# buisiness_card.net
KiCad netlist of a schematic drawn in EAGLE
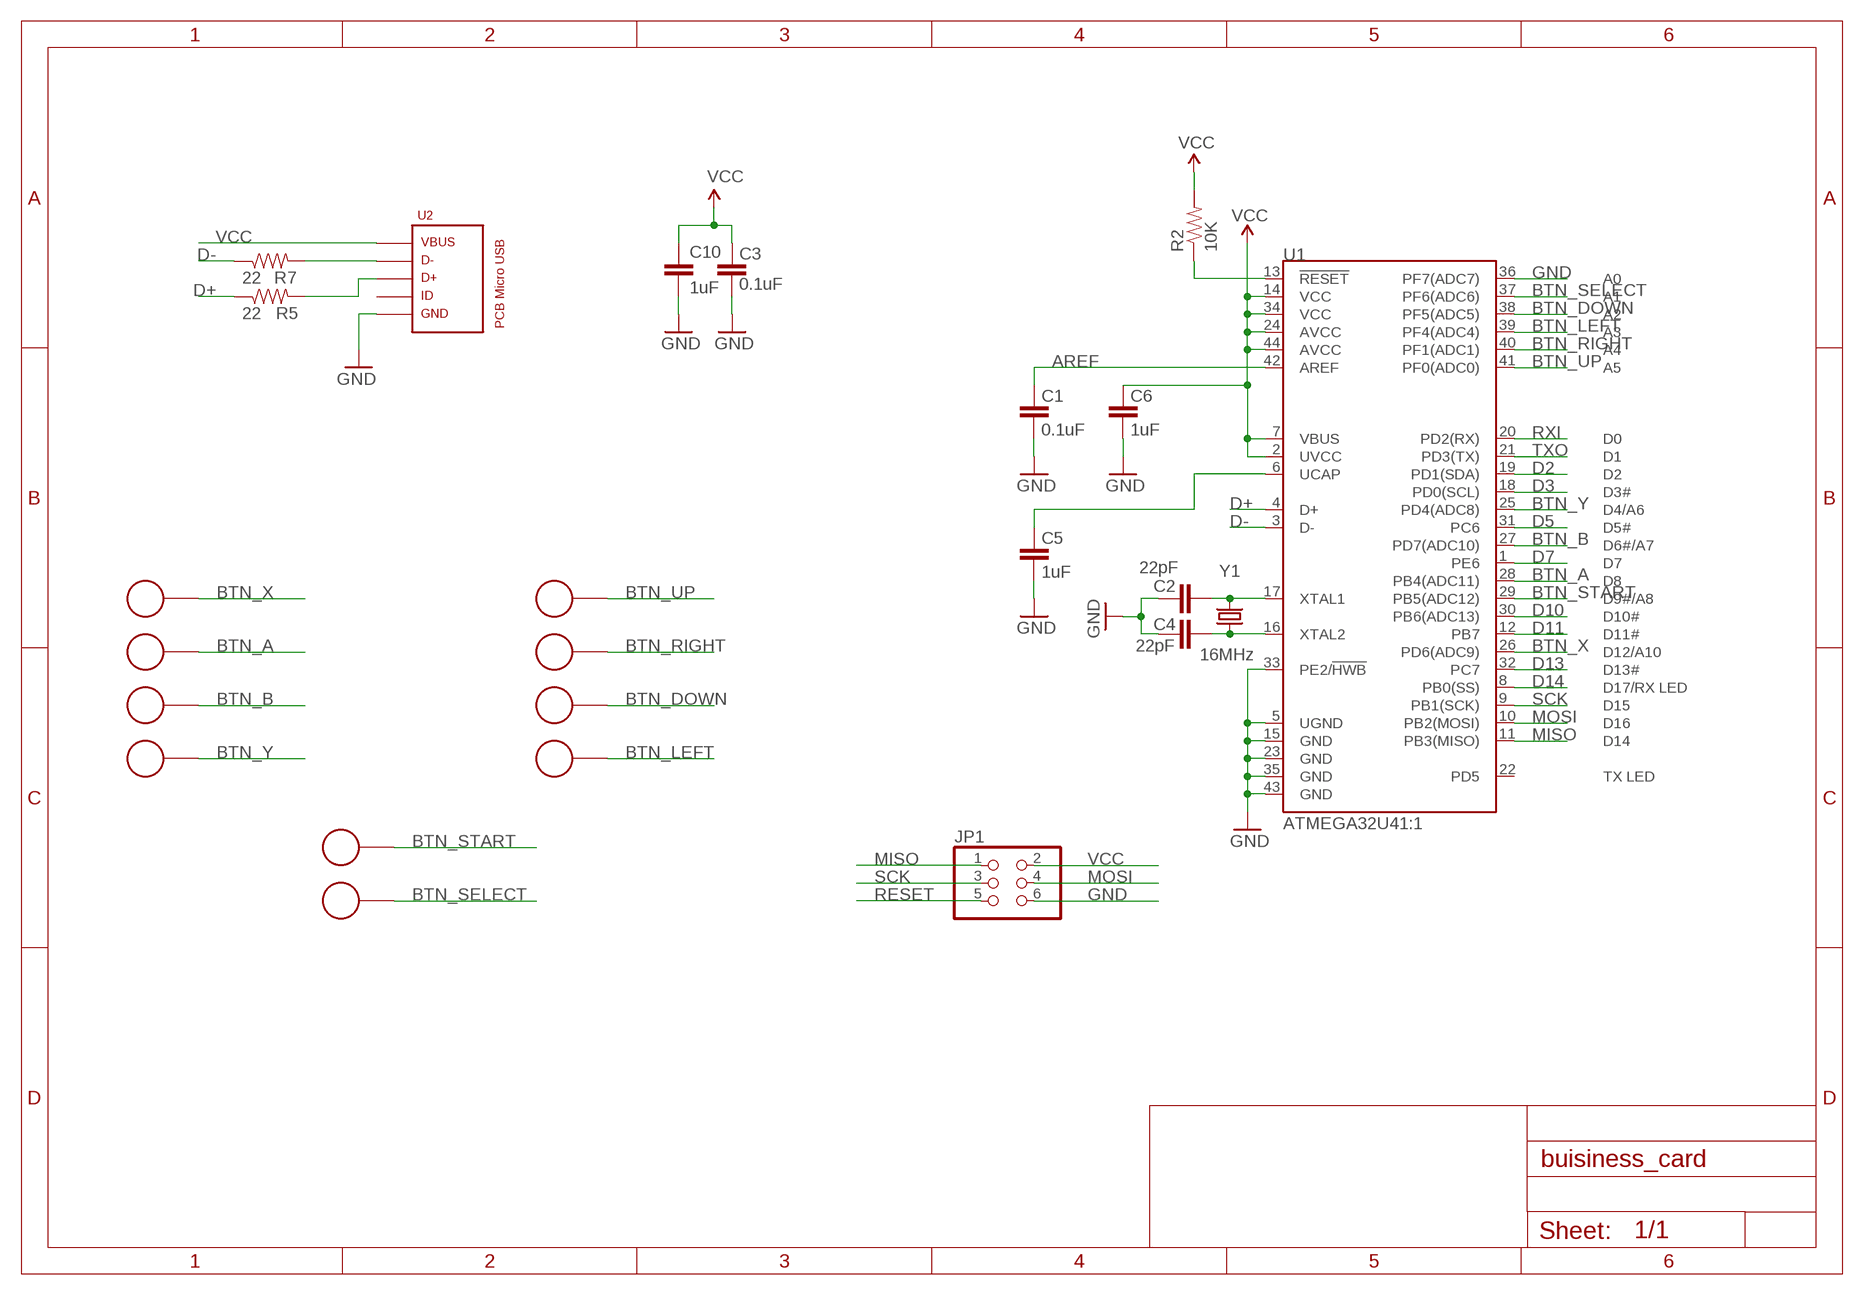
[diagram p0: schematic, sheet 1]

(export (version "E")
  (design (tool "Eeschema 10.0.6"))
  (components
    (comp (ref "B1")
      (value "CAPACITIVE_BUTTON")
      (footprint "eagle-import:ROUND_CAP_BUTTON")
      (libsource (lib "eagle-import") (part "CAPACITIVE_BUTTON"))
    )
    (comp (ref "B2")
      (value "CAPACITIVE_BUTTON")
      (footprint "eagle-import:ROUND_CAP_BUTTON")
      (libsource (lib "eagle-import") (part "CAPACITIVE_BUTTON"))
    )
    (comp (ref "B3")
      (value "CAPACITIVE_BUTTON")
      (footprint "eagle-import:ROUND_CAP_BUTTON")
      (libsource (lib "eagle-import") (part "CAPACITIVE_BUTTON"))
    )
    (comp (ref "B4")
      (value "CAPACITIVE_BUTTON")
      (footprint "eagle-import:ROUND_CAP_BUTTON")
      (libsource (lib "eagle-import") (part "CAPACITIVE_BUTTON"))
    )
    (comp (ref "B5")
      (value "CAPACITIVE_BUTTON")
      (footprint "eagle-import:ROUND_CAP_BUTTON")
      (libsource (lib "eagle-import") (part "CAPACITIVE_BUTTON"))
    )
    (comp (ref "B6")
      (value "CAPACITIVE_BUTTON")
      (footprint "eagle-import:ROUND_CAP_BUTTON")
      (libsource (lib "eagle-import") (part "CAPACITIVE_BUTTON"))
    )
    (comp (ref "B7")
      (value "CAPACITIVE_BUTTON")
      (footprint "eagle-import:ROUND_CAP_BUTTON")
      (libsource (lib "eagle-import") (part "CAPACITIVE_BUTTON"))
    )
    (comp (ref "B8")
      (value "CAPACITIVE_BUTTON")
      (footprint "eagle-import:ROUND_CAP_BUTTON")
      (libsource (lib "eagle-import") (part "CAPACITIVE_BUTTON"))
    )
    (comp (ref "B9")
      (value "CAPACITIVE_BUTTON")
      (footprint "eagle-import:ROUND_CAP_BUTTON")
      (libsource (lib "eagle-import") (part "CAPACITIVE_BUTTON"))
    )
    (comp (ref "B10")
      (value "CAPACITIVE_BUTTON")
      (footprint "eagle-import:ROUND_CAP_BUTTON")
      (libsource (lib "eagle-import") (part "CAPACITIVE_BUTTON"))
    )
    (comp (ref "C1")
      (value "0.1uF")
      (footprint "eagle-import:0603-CAP")
      (libsource (lib "eagle-import") (part "CAP0603-CAP"))
    )
    (comp (ref "C2")
      (value "22pF")
      (footprint "eagle-import:0603-CAP")
      (libsource (lib "eagle-import") (part "CAP0603-CAP"))
    )
    (comp (ref "C3")
      (value "0.1uF")
      (footprint "eagle-import:0603-CAP")
      (libsource (lib "eagle-import") (part "CAP0603-CAP"))
    )
    (comp (ref "C4")
      (value "22pF")
      (footprint "eagle-import:0603-CAP")
      (libsource (lib "eagle-import") (part "CAP0603-CAP"))
    )
    (comp (ref "C5")
      (value "1uF")
      (footprint "eagle-import:0603-CAP")
      (libsource (lib "eagle-import") (part "CAP0603-CAP"))
    )
    (comp (ref "C6")
      (value "1uF")
      (footprint "eagle-import:0603-CAP")
      (libsource (lib "eagle-import") (part "CAP0603-CAP"))
    )
    (comp (ref "C10")
      (value "1uF")
      (footprint "eagle-import:0603-CAP")
      (libsource (lib "eagle-import") (part "CAP0603-CAP"))
    )
    (comp (ref "JP1")
      (value "PINHD-2X3")
      (footprint "eagle-import:2X03")
      (libsource (lib "eagle-import") (part "PINHD-2X3"))
    )
    (comp (ref "R2")
      (value "10K")
      (footprint "eagle-import:0603-RES")
      (libsource (lib "eagle-import") (part "RESISTOR0603-RES"))
    )
    (comp (ref "R5")
      (value "22")
      (footprint "eagle-import:0603-RES")
      (libsource (lib "eagle-import") (part "RESISTOR0603-RES"))
    )
    (comp (ref "R7")
      (value "22")
      (footprint "eagle-import:0603-RES")
      (libsource (lib "eagle-import") (part "RESISTOR0603-RES"))
    )
    (comp (ref "U1")
      (value "ATMEGA32U41:1")
      (footprint "eagle-import:QFN-44-NOPAD_1_1")
      (libsource (lib "eagle-import") (part "ATMEGA32U41{colon}1"))
    )
    (comp (ref "U2")
      (value "PCB_MICRO_USB_BSS_2")
      (footprint "eagle-import:USB_TYPE_B_SS_2")
      (libsource (lib "eagle-import") (part "PCB_MICRO_USB_BSS_2"))
    )
    (comp (ref "Y1")
      (value "16MHz")
      (footprint "eagle-import:CRYSTAL-SMD-5X3")
      (libsource (lib "eagle-import") (part "CRYSTAL5X3"))
    )
  )
  (nets
    (net (code "1") (name "/AREF") (class "Default")
      (node (ref "C1") (pin "2") (pinfunction "2_2") (pintype "passive"))
      (node (ref "U1") (pin "42") (pinfunction "AREF_42") (pintype "bidirectional"))
    )
    (net (code "2") (name "/BTN_A") (class "Default")
      (node (ref "B2") (pin "P$1") (pinfunction "P$1_P$1") (pintype "output"))
      (node (ref "U1") (pin "28") (pinfunction "PB4(ADC11)_28") (pintype "bidirectional"))
    )
    (net (code "3") (name "/BTN_B") (class "Default")
      (node (ref "B3") (pin "P$1") (pinfunction "P$1_P$1") (pintype "output"))
      (node (ref "U1") (pin "27") (pinfunction "PD7(ADC10)_27") (pintype "bidirectional"))
    )
    (net (code "4") (name "/BTN_DOWN") (class "Default")
      (node (ref "B7") (pin "P$1") (pinfunction "P$1_P$1") (pintype "output"))
      (node (ref "U1") (pin "38") (pinfunction "PF5(ADC5)_38") (pintype "bidirectional"))
    )
    (net (code "5") (name "/BTN_LEFT") (class "Default")
      (node (ref "B8") (pin "P$1") (pinfunction "P$1_P$1") (pintype "output"))
      (node (ref "U1") (pin "39") (pinfunction "PF4(ADC4)_39") (pintype "bidirectional"))
    )
    (net (code "6") (name "/BTN_RIGHT") (class "Default")
      (node (ref "B6") (pin "P$1") (pinfunction "P$1_P$1") (pintype "output"))
      (node (ref "U1") (pin "40") (pinfunction "PF1(ADC1)_40") (pintype "bidirectional"))
    )
    (net (code "7") (name "/BTN_SELECT") (class "Default")
      (node (ref "B10") (pin "P$1") (pinfunction "P$1_P$1") (pintype "output"))
      (node (ref "U1") (pin "37") (pinfunction "PF6(ADC6)_37") (pintype "bidirectional"))
    )
    (net (code "8") (name "/BTN_START") (class "Default")
      (node (ref "B9") (pin "P$1") (pinfunction "P$1_P$1") (pintype "output"))
      (node (ref "U1") (pin "29") (pinfunction "PB5(ADC12)_29") (pintype "bidirectional"))
    )
    (net (code "9") (name "/BTN_UP") (class "Default")
      (node (ref "B5") (pin "P$1") (pinfunction "P$1_P$1") (pintype "output"))
      (node (ref "U1") (pin "41") (pinfunction "PF0(ADC0)_41") (pintype "bidirectional"))
    )
    (net (code "10") (name "/BTN_X") (class "Default")
      (node (ref "B1") (pin "P$1") (pinfunction "P$1_P$1") (pintype "output"))
      (node (ref "U1") (pin "26") (pinfunction "PD6(ADC9)_26") (pintype "bidirectional"))
    )
    (net (code "11") (name "/BTN_Y") (class "Default")
      (node (ref "B4") (pin "P$1") (pinfunction "P$1_P$1") (pintype "output"))
      (node (ref "U1") (pin "25") (pinfunction "PD4(ADC8)_25") (pintype "bidirectional"))
    )
    (net (code "12") (name "/D+") (class "Default")
      (node (ref "R5") (pin "1") (pinfunction "1_1") (pintype "passive"))
      (node (ref "U1") (pin "4") (pinfunction "D+_4") (pintype "bidirectional"))
    )
    (net (code "13") (name "/D-") (class "Default")
      (node (ref "R7") (pin "1") (pinfunction "1_1") (pintype "passive"))
      (node (ref "U1") (pin "3") (pinfunction "D-_3") (pintype "bidirectional"))
    )
    (net (code "14") (name "/D2") (class "Default")
      (node (ref "U1") (pin "19") (pinfunction "PD1(SDA)_19") (pintype "bidirectional"))
    )
    (net (code "15") (name "/D3") (class "Default")
      (node (ref "U1") (pin "18") (pinfunction "PD0(SCL)_18") (pintype "bidirectional"))
    )
    (net (code "16") (name "/D5") (class "Default")
      (node (ref "U1") (pin "31") (pinfunction "PC6_31") (pintype "bidirectional"))
    )
    (net (code "17") (name "/D7") (class "Default")
      (node (ref "U1") (pin "1") (pinfunction "PE6_1") (pintype "bidirectional"))
    )
    (net (code "18") (name "/D10") (class "Default")
      (node (ref "U1") (pin "30") (pinfunction "PB6(ADC13)_30") (pintype "bidirectional"))
    )
    (net (code "19") (name "/D11") (class "Default")
      (node (ref "U1") (pin "12") (pinfunction "PB7_12") (pintype "bidirectional"))
    )
    (net (code "20") (name "/D13") (class "Default")
      (node (ref "U1") (pin "32") (pinfunction "PC7_32") (pintype "bidirectional"))
    )
    (net (code "21") (name "/D14") (class "Default")
      (node (ref "U1") (pin "8") (pinfunction "PB0(SS)_8") (pintype "bidirectional"))
    )
    (net (code "22") (name "/MISO") (class "Default")
      (node (ref "JP1") (pin "1") (pinfunction "1_1") (pintype "passive"))
      (node (ref "U1") (pin "11") (pinfunction "PB3(MISO)_11") (pintype "bidirectional"))
    )
    (net (code "23") (name "/MOSI") (class "Default")
      (node (ref "JP1") (pin "4") (pinfunction "4_4") (pintype "passive"))
      (node (ref "U1") (pin "10") (pinfunction "PB2(MOSI)_10") (pintype "bidirectional"))
    )
    (net (code "24") (name "/RESET") (class "Default")
      (node (ref "JP1") (pin "5") (pinfunction "5_5") (pintype "passive"))
      (node (ref "R2") (pin "1") (pinfunction "1_1") (pintype "passive"))
      (node (ref "U1") (pin "13") (pinfunction "~{RESET}_13") (pintype "bidirectional"))
    )
    (net (code "25") (name "/RXI") (class "Default")
      (node (ref "U1") (pin "20") (pinfunction "PD2(RX)_20") (pintype "bidirectional"))
    )
    (net (code "26") (name "/SCK") (class "Default")
      (node (ref "JP1") (pin "3") (pinfunction "3_3") (pintype "passive"))
      (node (ref "U1") (pin "9") (pinfunction "PB1(SCK)_9") (pintype "bidirectional"))
    )
    (net (code "27") (name "/TXO") (class "Default")
      (node (ref "U1") (pin "21") (pinfunction "PD3(TX)_21") (pintype "bidirectional"))
    )
    (net (code "28") (name "GND") (class "Default")
      (node (ref "C1") (pin "1") (pinfunction "1_1") (pintype "passive"))
      (node (ref "C10") (pin "2") (pinfunction "2_2") (pintype "passive"))
      (node (ref "C2") (pin "2") (pinfunction "2_2") (pintype "passive"))
      (node (ref "C3") (pin "1") (pinfunction "1_1") (pintype "passive"))
      (node (ref "C4") (pin "2") (pinfunction "2_2") (pintype "passive"))
      (node (ref "C5") (pin "1") (pinfunction "1_1") (pintype "passive"))
      (node (ref "C6") (pin "1") (pinfunction "1_1") (pintype "passive"))
      (node (ref "JP1") (pin "6") (pinfunction "6_6") (pintype "passive"))
      (node (ref "U1") (pin "15") (pinfunction "GND_15") (pintype "bidirectional"))
      (node (ref "U1") (pin "23") (pinfunction "GND_23") (pintype "bidirectional"))
      (node (ref "U1") (pin "33") (pinfunction "PE2/~{HWB}_33") (pintype "bidirectional"))
      (node (ref "U1") (pin "35") (pinfunction "GND_35") (pintype "bidirectional"))
      (node (ref "U1") (pin "36") (pinfunction "PF7(ADC7)_36") (pintype "bidirectional"))
      (node (ref "U1") (pin "43") (pinfunction "GND_43") (pintype "bidirectional"))
      (node (ref "U1") (pin "5") (pinfunction "UGND_5") (pintype "bidirectional"))
      (node (ref "U2") (pin "5") (pinfunction "5_5") (pintype "bidirectional"))
    )
    (net (code "29") (name "Net-(R5-Pad2)") (class "Default")
      (node (ref "R5") (pin "2") (pinfunction "2_2") (pintype "passive"))
      (node (ref "U2") (pin "3") (pinfunction "3_3") (pintype "bidirectional"))
    )
    (net (code "30") (name "Net-(R7-Pad2)") (class "Default")
      (node (ref "R7") (pin "2") (pinfunction "2_2") (pintype "passive"))
      (node (ref "U2") (pin "2") (pinfunction "2_2") (pintype "bidirectional"))
    )
    (net (code "31") (name "Net-(U1-UCAP)") (class "Default")
      (node (ref "C5") (pin "2") (pinfunction "2_2") (pintype "passive"))
      (node (ref "U1") (pin "6") (pinfunction "UCAP_6") (pintype "bidirectional"))
    )
    (net (code "32") (name "Net-(U1-XTAL1)") (class "Default")
      (node (ref "C2") (pin "1") (pinfunction "1_1") (pintype "passive"))
      (node (ref "U1") (pin "17") (pinfunction "XTAL1_17") (pintype "bidirectional"))
      (node (ref "Y1") (pin "3") (pinfunction "2_3") (pintype "passive"))
    )
    (net (code "33") (name "Net-(U1-XTAL2)") (class "Default")
      (node (ref "C4") (pin "1") (pinfunction "1_1") (pintype "passive"))
      (node (ref "U1") (pin "16") (pinfunction "XTAL2_16") (pintype "bidirectional"))
      (node (ref "Y1") (pin "1") (pinfunction "1_1") (pintype "passive"))
    )
    (net (code "34") (name "VCC") (class "Default")
      (node (ref "C10") (pin "1") (pinfunction "1_1") (pintype "passive"))
      (node (ref "C3") (pin "2") (pinfunction "2_2") (pintype "passive"))
      (node (ref "C6") (pin "2") (pinfunction "2_2") (pintype "passive"))
      (node (ref "JP1") (pin "2") (pinfunction "2_2") (pintype "passive"))
      (node (ref "R2") (pin "2") (pinfunction "2_2") (pintype "passive"))
      (node (ref "U1") (pin "14") (pinfunction "VCC_14") (pintype "bidirectional"))
      (node (ref "U1") (pin "2") (pinfunction "UVCC_2") (pintype "bidirectional"))
      (node (ref "U1") (pin "24") (pinfunction "AVCC_24") (pintype "bidirectional"))
      (node (ref "U1") (pin "34") (pinfunction "VCC_34") (pintype "bidirectional"))
      (node (ref "U1") (pin "44") (pinfunction "AVCC_44") (pintype "bidirectional"))
      (node (ref "U1") (pin "7") (pinfunction "VBUS_7") (pintype "bidirectional"))
      (node (ref "U2") (pin "1") (pinfunction "1_1") (pintype "bidirectional"))
    )
    (net (code "35") (name "unconnected-(U1-PD5-Pad22)") (class "Default")
      (node (ref "U1") (pin "22") (pinfunction "PD5_22") (pintype "bidirectional"))
    )
    (net (code "36") (name "unconnected-(U2-Pad4)") (class "Default")
      (node (ref "U2") (pin "4") (pinfunction "4_4") (pintype "bidirectional"))
    )
  )
)
